# JM_Logics_I2C_SMD_Adapter_v1_4.net
KiCad netlist of a schematic drawn in EAGLE
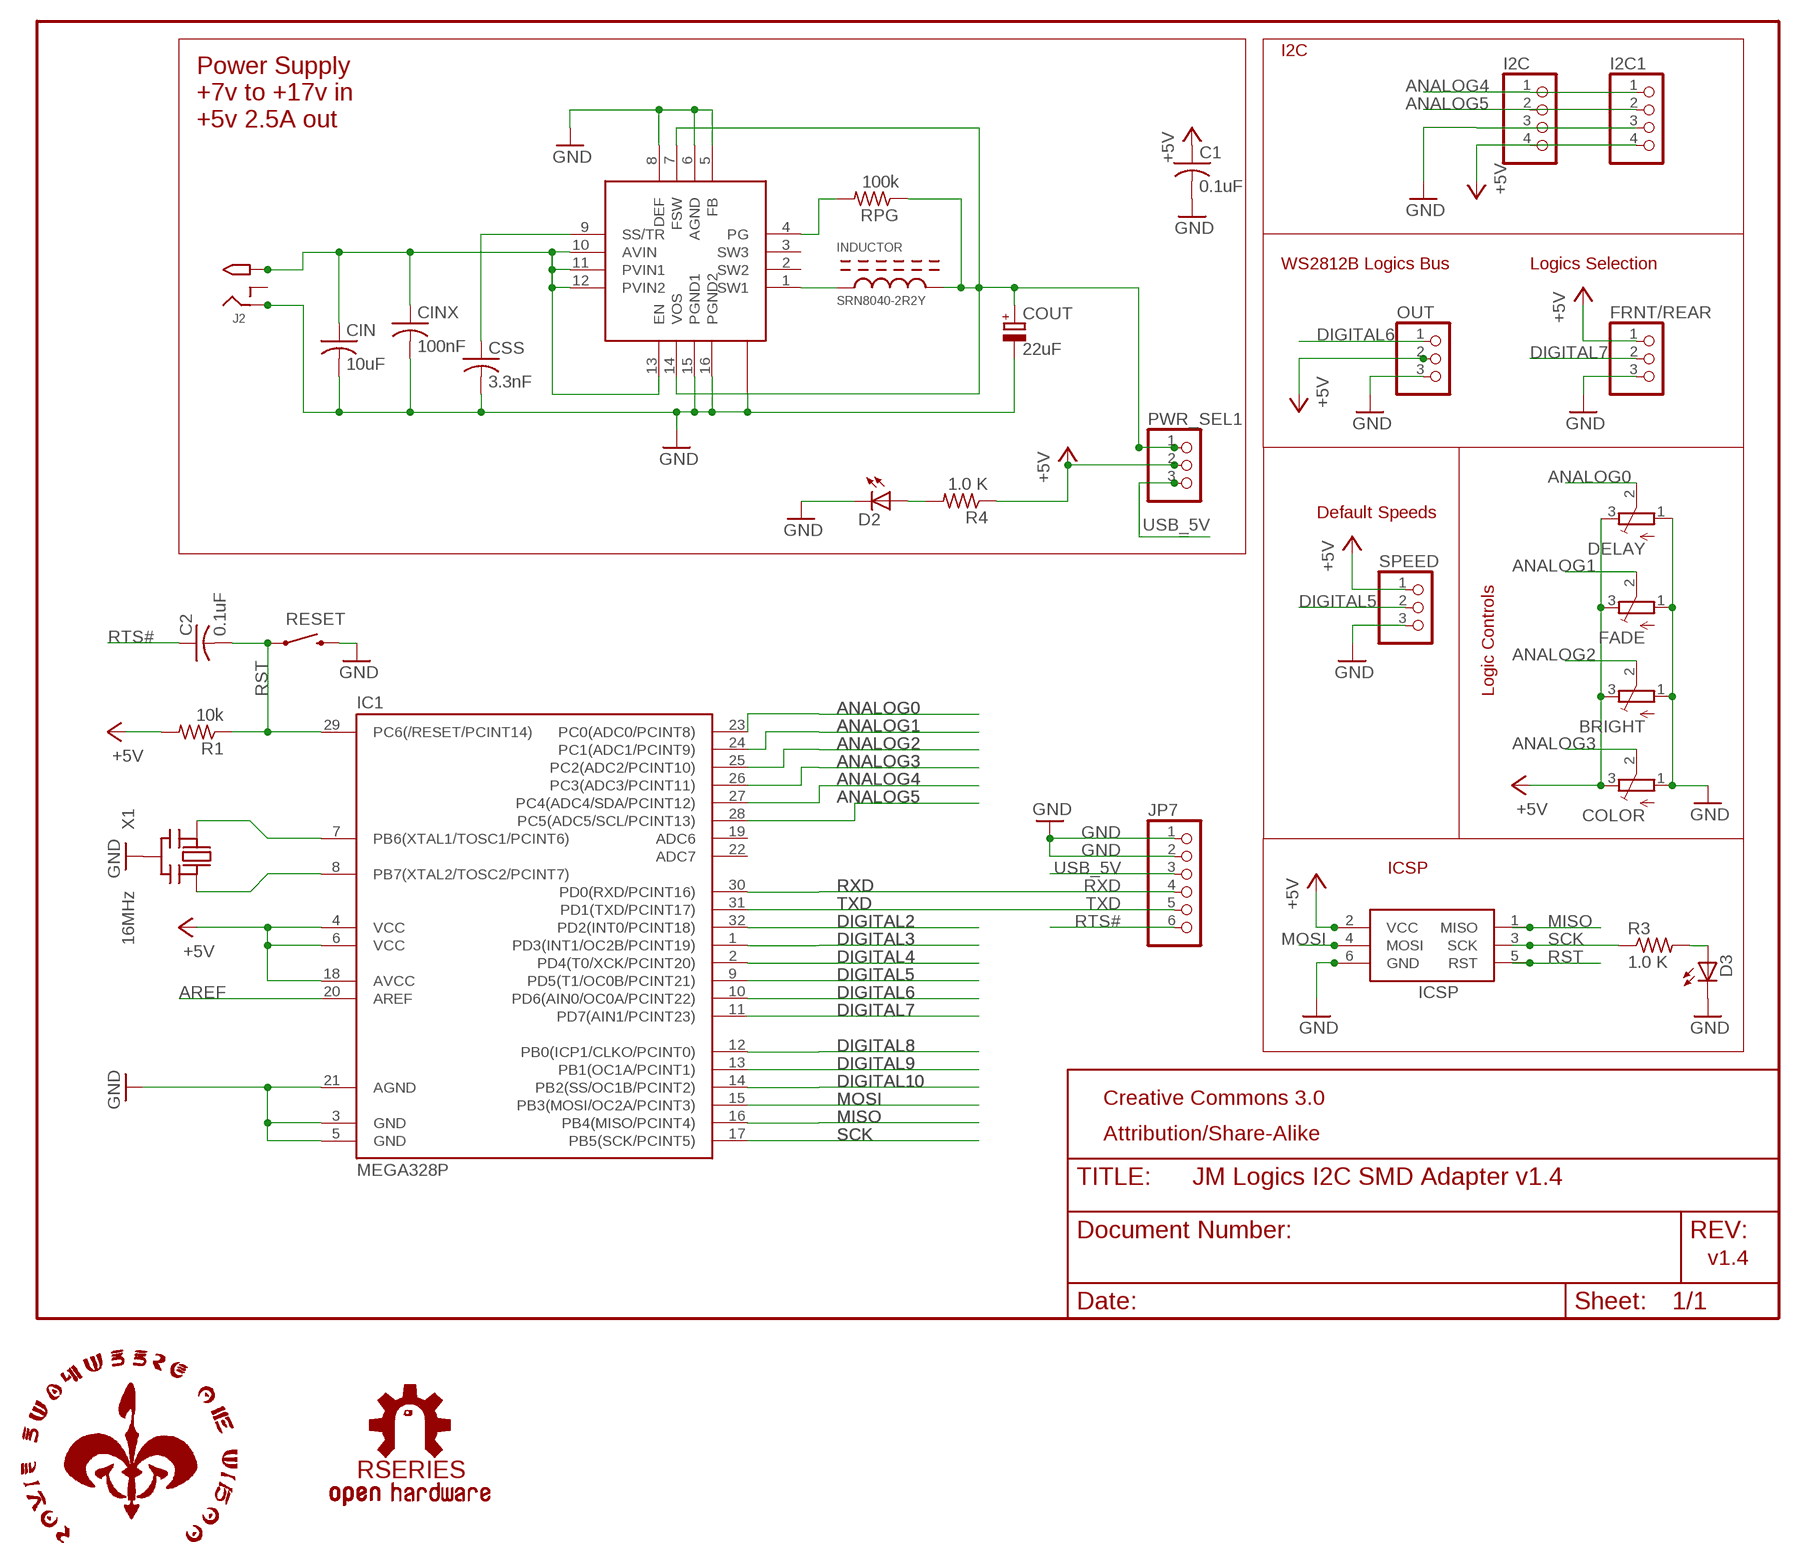
[diagram p0: schematic, sheet 1]

(export (version "E")
  (design (tool "Eeschema 10.0.6"))
  (components
    (comp (ref "BRIGHT")
      (value "TRIMPOTTC33X")
      (footprint "eagle-import:TC33X")
      (libsource (lib "eagle-import") (part "TRIMPOTTC33X"))
    )
    (comp (ref "C1")
      (value "0.1uF")
      (footprint "eagle-import:C1206K")
      (libsource (lib "eagle-import") (part "minimidi_C-USC1206K"))
    )
    (comp (ref "C2")
      (value "0.1uF")
      (footprint "eagle-import:C0805K")
      (libsource (lib "eagle-import") (part "C-USC0805K"))
    )
    (comp (ref "CIN")
      (value "10uF")
      (footprint "eagle-import:C0805K")
      (libsource (lib "eagle-import") (part "C-USC0805K"))
    )
    (comp (ref "CINX")
      (value "100nF")
      (footprint "eagle-import:C0805K")
      (libsource (lib "eagle-import") (part "C-USC0805K"))
    )
    (comp (ref "COLOR")
      (value "TRIMPOTTC33X")
      (footprint "eagle-import:TC33X")
      (libsource (lib "eagle-import") (part "TRIMPOTTC33X"))
    )
    (comp (ref "COUT")
      (value "22uF")
      (footprint "eagle-import:CASE_B")
      (libsource (lib "eagle-import") (part "CAPACITOR_POL-CASE_B"))
    )
    (comp (ref "CSS")
      (value "3.3nF")
      (footprint "eagle-import:C0805K")
      (libsource (lib "eagle-import") (part "C-USC0805K"))
    )
    (comp (ref "D2")
      (value "LEDCHIPLED_1206")
      (footprint "eagle-import:CHIPLED_1206")
      (libsource (lib "eagle-import") (part "LEDCHIPLED_1206"))
    )
    (comp (ref "D3")
      (value "Green")
      (footprint "eagle-import:CHIPLED_1206")
      (libsource (lib "eagle-import") (part "LEDCHIPLED_1206"))
    )
    (comp (ref "DELAY")
      (value "TRIMPOTTC33X")
      (footprint "eagle-import:TC33X")
      (libsource (lib "eagle-import") (part "TRIMPOTTC33X"))
    )
    (comp (ref "FADE")
      (value "TRIMPOTTC33X")
      (footprint "eagle-import:TC33X")
      (libsource (lib "eagle-import") (part "TRIMPOTTC33X"))
    )
    (comp (ref "FRNT/REAR")
      (value "PINHD-1X3")
      (footprint "eagle-import:1X03")
      (libsource (lib "eagle-import") (part "PINHD-1X3"))
    )
    (comp (ref "I2C")
      (value "PINHD-1X4CB")
      (footprint "eagle-import:1X04-CB")
      (libsource (lib "eagle-import") (part "PINHD-1X4CB"))
    )
    (comp (ref "I2C1")
      (value "PINHD-1X4CB")
      (footprint "eagle-import:1X04-CB")
      (libsource (lib "eagle-import") (part "PINHD-1X4CB"))
    )
    (comp (ref "IC1")
      (value "MEGA328P")
      (footprint "eagle-import:TQFP32-08")
      (libsource (lib "eagle-import") (part "MEGA48/88/168-AU"))
    )
    (comp (ref "ICSP")
      (value "AVRISP-6")
      (footprint "eagle-import:AVRISP")
      (libsource (lib "eagle-import") (part "AVRISP-6"))
    )
    (comp (ref "INDUCTOR")
      (value "SRN8040-2R2Y")
      (footprint "eagle-import:SRN8040")
      (libsource (lib "eagle-import") (part "SRN8040"))
    )
    (comp (ref "J2")
      (value "2.1MMJACK")
      (footprint "eagle-import:PJ-102A")
      (libsource (lib "eagle-import") (part "2.1MMJACK"))
    )
    (comp (ref "JP7")
      (value "PINHD-1X6CLEAN")
      (footprint "eagle-import:1X06-CLEAN")
      (libsource (lib "eagle-import") (part "PINHD-1X6CLEAN"))
    )
    (comp (ref "OUT")
      (value "PINHD-1X3")
      (footprint "eagle-import:1X03")
      (libsource (lib "eagle-import") (part "PINHD-1X3"))
    )
    (comp (ref "PWR_SEL1")
      (value "PINHD-1X3")
      (footprint "eagle-import:1X03")
      (libsource (lib "eagle-import") (part "PINHD-1X3"))
    )
    (comp (ref "R1")
      (value "10k")
      (footprint "eagle-import:R0805")
      (libsource (lib "eagle-import") (part "R-US_R0805"))
    )
    (comp (ref "R3")
      (value "1.0 K")
      (footprint "eagle-import:M1206")
      (libsource (lib "eagle-import") (part "minimidi_R-US_M1206"))
    )
    (comp (ref "R4")
      (value "1.0 K")
      (footprint "eagle-import:M1206")
      (libsource (lib "eagle-import") (part "minimidi_R-US_M1206"))
    )
    (comp (ref "REG")
      (value "TPS62133")
      (footprint "eagle-import:TPS6213X")
      (libsource (lib "eagle-import") (part "TPS6213X"))
    )
    (comp (ref "RESET")
      (value "SWITCH-MOMENTARY-2SMD")
      (footprint "eagle-import:TACTILE_SWITCH_SMD")
      (libsource (lib "eagle-import") (part "SWITCH-MOMENTARY-2SMD"))
    )
    (comp (ref "RPG")
      (value "100k")
      (footprint "eagle-import:R0805")
      (libsource (lib "eagle-import") (part "R-US_R0805"))
    )
    (comp (ref "SPEED")
      (value "PINHD-1X3")
      (footprint "eagle-import:1X03")
      (libsource (lib "eagle-import") (part "PINHD-1X3"))
    )
    (comp (ref "U$1")
      (value "ROYAL-ENGINEERS-OF-NABOOSMALL")
      (footprint "eagle-import:ROYAL-ENGINEERS-OF-NABOO-SMALL")
      (libsource (lib "eagle-import") (part "ROYAL-ENGINEERS-OF-NABOOSMALL"))
    )
    (comp (ref "U$2")
      (value "RSERIES-OSHW-LOGOMEDIUM")
      (footprint "eagle-import:RSERIES-OSHW-LOGO-MEDIUM")
      (libsource (lib "eagle-import") (part "RSERIES-OSHW-LOGOMEDIUM"))
    )
    (comp (ref "X1")
      (value "16MHz")
      (footprint "eagle-import:CERM_OSC")
      (libsource (lib "eagle-import") (part "CERMOSCILL"))
    )
  )
  (nets
    (net (code "1") (name "+5V") (class "Default")
      (node (ref "BRIGHT") (pin "3") (pinfunction "E_3") (pintype "passive"))
      (node (ref "C1") (pin "1") (pinfunction "1_1") (pintype "passive"))
      (node (ref "COLOR") (pin "3") (pinfunction "E_3") (pintype "passive"))
      (node (ref "DELAY") (pin "3") (pinfunction "E_3") (pintype "passive"))
      (node (ref "FADE") (pin "3") (pinfunction "E_3") (pintype "passive"))
      (node (ref "FRNT/REAR") (pin "1") (pinfunction "1_1") (pintype "passive"))
      (node (ref "I2C") (pin "4") (pinfunction "4_4") (pintype "passive"))
      (node (ref "I2C1") (pin "4") (pinfunction "4_4") (pintype "passive"))
      (node (ref "IC1") (pin "18") (pinfunction "AVCC_18") (pintype "passive"))
      (node (ref "IC1") (pin "4") (pinfunction "VCC_4") (pintype "power_in"))
      (node (ref "IC1") (pin "6") (pinfunction "VCC_6") (pintype "power_in"))
      (node (ref "ICSP") (pin "2") (pinfunction "VCC_2") (pintype "power_in"))
      (node (ref "OUT") (pin "2") (pinfunction "2_2") (pintype "passive"))
      (node (ref "PWR_SEL1") (pin "2") (pinfunction "2_2") (pintype "passive"))
      (node (ref "R1") (pin "2") (pinfunction "2_2") (pintype "passive"))
      (node (ref "R4") (pin "1") (pinfunction "1_1") (pintype "passive"))
      (node (ref "SPEED") (pin "1") (pinfunction "1_1") (pintype "passive"))
    )
    (net (code "2") (name "/ANALOG0") (class "Default")
      (node (ref "DELAY") (pin "2") (pinfunction "S_2") (pintype "passive"))
      (node (ref "IC1") (pin "23") (pinfunction "PC0(ADC0/PCINT8)_23") (pintype "bidirectional"))
    )
    (net (code "3") (name "/ANALOG1") (class "Default")
      (node (ref "FADE") (pin "2") (pinfunction "S_2") (pintype "passive"))
      (node (ref "IC1") (pin "24") (pinfunction "PC1(ADC1/PCINT9)_24") (pintype "bidirectional"))
    )
    (net (code "4") (name "/ANALOG2") (class "Default")
      (node (ref "BRIGHT") (pin "2") (pinfunction "S_2") (pintype "passive"))
      (node (ref "IC1") (pin "25") (pinfunction "PC2(ADC2/PCINT10)_25") (pintype "bidirectional"))
    )
    (net (code "5") (name "/ANALOG3") (class "Default")
      (node (ref "COLOR") (pin "2") (pinfunction "S_2") (pintype "passive"))
      (node (ref "IC1") (pin "26") (pinfunction "PC3(ADC3/PCINT11)_26") (pintype "bidirectional"))
    )
    (net (code "6") (name "/ANALOG4") (class "Default")
      (node (ref "I2C") (pin "1") (pinfunction "1_1") (pintype "passive"))
      (node (ref "I2C1") (pin "1") (pinfunction "1_1") (pintype "passive"))
      (node (ref "IC1") (pin "27") (pinfunction "PC4(ADC4/SDA/PCINT12)_27") (pintype "bidirectional"))
    )
    (net (code "7") (name "/ANALOG5") (class "Default")
      (node (ref "I2C") (pin "2") (pinfunction "2_2") (pintype "passive"))
      (node (ref "I2C1") (pin "2") (pinfunction "2_2") (pintype "passive"))
      (node (ref "IC1") (pin "28") (pinfunction "PC5(ADC5/SCL/PCINT13)_28") (pintype "bidirectional"))
    )
    (net (code "8") (name "/AREF") (class "Default")
      (node (ref "IC1") (pin "20") (pinfunction "AREF_20") (pintype "passive"))
    )
    (net (code "9") (name "/DIGITAL2") (class "Default")
      (node (ref "IC1") (pin "32") (pinfunction "PD2(INT0/PCINT18)_32") (pintype "bidirectional"))
    )
    (net (code "10") (name "/DIGITAL3") (class "Default")
      (node (ref "IC1") (pin "1") (pinfunction "PD3(INT1/OC2B/PCINT19)_1") (pintype "bidirectional"))
    )
    (net (code "11") (name "/DIGITAL4") (class "Default")
      (node (ref "IC1") (pin "2") (pinfunction "PD4(T0/XCK/PCINT20)_2") (pintype "bidirectional"))
    )
    (net (code "12") (name "/DIGITAL5") (class "Default")
      (node (ref "IC1") (pin "9") (pinfunction "PD5(T1/OC0B/PCINT21)_9") (pintype "bidirectional"))
      (node (ref "SPEED") (pin "2") (pinfunction "2_2") (pintype "passive"))
    )
    (net (code "13") (name "/DIGITAL6") (class "Default")
      (node (ref "IC1") (pin "10") (pinfunction "PD6(AIN0/OC0A/PCINT22)_10") (pintype "bidirectional"))
      (node (ref "OUT") (pin "1") (pinfunction "1_1") (pintype "passive"))
    )
    (net (code "14") (name "/DIGITAL7") (class "Default")
      (node (ref "FRNT/REAR") (pin "2") (pinfunction "2_2") (pintype "passive"))
      (node (ref "IC1") (pin "11") (pinfunction "PD7(AIN1/PCINT23)_11") (pintype "bidirectional"))
    )
    (net (code "15") (name "/DIGITAL8") (class "Default")
      (node (ref "IC1") (pin "12") (pinfunction "PB0(ICP1/CLKO/PCINT0)_12") (pintype "bidirectional"))
    )
    (net (code "16") (name "/DIGITAL9") (class "Default")
      (node (ref "IC1") (pin "13") (pinfunction "PB1(OC1A/PCINT1)_13") (pintype "bidirectional"))
    )
    (net (code "17") (name "/DIGITAL10") (class "Default")
      (node (ref "IC1") (pin "14") (pinfunction "PB2(SS/OC1B/PCINT2)_14") (pintype "bidirectional"))
    )
    (net (code "18") (name "/MISO") (class "Default")
      (node (ref "IC1") (pin "16") (pinfunction "PB4(MISO/PCINT4)_16") (pintype "bidirectional"))
      (node (ref "ICSP") (pin "1") (pinfunction "MISO_1") (pintype "input"))
    )
    (net (code "19") (name "/MOSI") (class "Default")
      (node (ref "IC1") (pin "15") (pinfunction "PB3(MOSI/OC2A/PCINT3)_15") (pintype "bidirectional"))
      (node (ref "ICSP") (pin "4") (pinfunction "MOSI_4") (pintype "output"))
    )
    (net (code "20") (name "/RST") (class "Default")
      (node (ref "C2") (pin "2") (pinfunction "2_2") (pintype "passive"))
      (node (ref "IC1") (pin "29") (pinfunction "PC6(/RESET/PCINT14)_29") (pintype "bidirectional"))
      (node (ref "ICSP") (pin "5") (pinfunction "RST_5") (pintype "output"))
      (node (ref "R1") (pin "1") (pinfunction "1_1") (pintype "passive"))
      (node (ref "RESET") (pin "1") (pinfunction "1_1") (pintype "passive"))
    )
    (net (code "21") (name "/RTS#") (class "Default")
      (node (ref "C2") (pin "1") (pinfunction "1_1") (pintype "passive"))
      (node (ref "JP7") (pin "6") (pinfunction "6_6") (pintype "passive"))
    )
    (net (code "22") (name "/RXD") (class "Default")
      (node (ref "IC1") (pin "30") (pinfunction "PD0(RXD/PCINT16)_30") (pintype "bidirectional"))
      (node (ref "JP7") (pin "4") (pinfunction "4_4") (pintype "passive"))
    )
    (net (code "23") (name "/SCK") (class "Default")
      (node (ref "IC1") (pin "17") (pinfunction "PB5(SCK/PCINT5)_17") (pintype "bidirectional"))
      (node (ref "ICSP") (pin "3") (pinfunction "SCK_3") (pintype "output"))
      (node (ref "R3") (pin "1") (pinfunction "1_1") (pintype "passive"))
    )
    (net (code "24") (name "/TXD") (class "Default")
      (node (ref "IC1") (pin "31") (pinfunction "PD1(TXD/PCINT17)_31") (pintype "bidirectional"))
      (node (ref "JP7") (pin "5") (pinfunction "5_5") (pintype "passive"))
    )
    (net (code "25") (name "/USB_5V") (class "Default")
      (node (ref "JP7") (pin "3") (pinfunction "3_3") (pintype "passive"))
      (node (ref "PWR_SEL1") (pin "3") (pinfunction "3_3") (pintype "passive"))
    )
    (net (code "26") (name "GND") (class "Default")
      (node (ref "BRIGHT") (pin "1") (pinfunction "A_1") (pintype "passive"))
      (node (ref "C1") (pin "2") (pinfunction "2_2") (pintype "passive"))
      (node (ref "CIN") (pin "2") (pinfunction "2_2") (pintype "passive"))
      (node (ref "CINX") (pin "2") (pinfunction "2_2") (pintype "passive"))
      (node (ref "COLOR") (pin "1") (pinfunction "A_1") (pintype "passive"))
      (node (ref "COUT") (pin "-") (pinfunction "-_-") (pintype "passive"))
      (node (ref "CSS") (pin "2") (pinfunction "2_2") (pintype "passive"))
      (node (ref "D2") (pin "C") (pinfunction "C_C") (pintype "passive"))
      (node (ref "D3") (pin "C") (pinfunction "C_C") (pintype "passive"))
      (node (ref "DELAY") (pin "1") (pinfunction "A_1") (pintype "passive"))
      (node (ref "FADE") (pin "1") (pinfunction "A_1") (pintype "passive"))
      (node (ref "FRNT/REAR") (pin "3") (pinfunction "3_3") (pintype "passive"))
      (node (ref "I2C") (pin "3") (pinfunction "3_3") (pintype "passive"))
      (node (ref "I2C1") (pin "3") (pinfunction "3_3") (pintype "passive"))
      (node (ref "IC1") (pin "21") (pinfunction "AGND_21") (pintype "power_in"))
      (node (ref "IC1") (pin "3") (pinfunction "GND_3") (pintype "power_in"))
      (node (ref "IC1") (pin "5") (pinfunction "GND_5") (pintype "power_in"))
      (node (ref "ICSP") (pin "6") (pinfunction "GND_6") (pintype "power_in"))
      (node (ref "J2") (pin "RING") (pinfunction "RING_RING") (pintype "bidirectional"))
      (node (ref "JP7") (pin "1") (pinfunction "1_1") (pintype "passive"))
      (node (ref "JP7") (pin "2") (pinfunction "2_2") (pintype "passive"))
      (node (ref "OUT") (pin "3") (pinfunction "3_3") (pintype "passive"))
      (node (ref "REG") (pin "15") (pinfunction "PGND1_15") (pintype "bidirectional"))
      (node (ref "REG") (pin "16") (pinfunction "PGND2_16") (pintype "bidirectional"))
      (node (ref "REG") (pin "17-THERMALPAD") (pinfunction "THERM_17-THERMALPAD") (pintype "bidirectional"))
      (node (ref "REG") (pin "5") (pinfunction "FB_5") (pintype "bidirectional"))
      (node (ref "REG") (pin "6") (pinfunction "AGND_6") (pintype "bidirectional"))
      (node (ref "REG") (pin "8") (pinfunction "DEF_8") (pintype "bidirectional"))
      (node (ref "RESET") (pin "3") (pinfunction "2_3") (pintype "passive"))
      (node (ref "SPEED") (pin "3") (pinfunction "3_3") (pintype "passive"))
      (node (ref "X1") (pin "P$2") (pinfunction "GND_P$2") (pintype "bidirectional"))
    )
    (net (code "27") (name "Net-(D2-PadA)") (class "Default")
      (node (ref "D2") (pin "A") (pinfunction "A_A") (pintype "passive"))
      (node (ref "R4") (pin "2") (pinfunction "2_2") (pintype "passive"))
    )
    (net (code "28") (name "Net-(D3-PadA)") (class "Default")
      (node (ref "D3") (pin "A") (pinfunction "A_A") (pintype "passive"))
      (node (ref "R3") (pin "2") (pinfunction "2_2") (pintype "passive"))
    )
    (net (code "29") (name "Net-(IC1-PB6(XTAL1{slash}TOSC1{slash}PCINT6))") (class "Default")
      (node (ref "IC1") (pin "7") (pinfunction "PB6(XTAL1/TOSC1/PCINT6)_7") (pintype "bidirectional"))
      (node (ref "X1") (pin "P$1") (pinfunction "IN_P$1") (pintype "bidirectional"))
    )
    (net (code "30") (name "Net-(IC1-PB7(XTAL2{slash}TOSC2{slash}PCINT7))") (class "Default")
      (node (ref "IC1") (pin "8") (pinfunction "PB7(XTAL2/TOSC2/PCINT7)_8") (pintype "bidirectional"))
      (node (ref "X1") (pin "P$3") (pinfunction "OUT_P$3") (pintype "bidirectional"))
    )
    (net (code "31") (name "Net-(INDUCTOR-P1)") (class "Default")
      (node (ref "INDUCTOR") (pin "P$1") (pinfunction "P1_P$1") (pintype "bidirectional"))
      (node (ref "REG") (pin "1") (pinfunction "SW1_1") (pintype "bidirectional"))
    )
    (net (code "32") (name "Net-(INDUCTOR-P2)") (class "Default")
      (node (ref "COUT") (pin "+") (pinfunction "+_+") (pintype "passive"))
      (node (ref "INDUCTOR") (pin "P$2") (pinfunction "P2_P$2") (pintype "bidirectional"))
      (node (ref "PWR_SEL1") (pin "1") (pinfunction "1_1") (pintype "passive"))
      (node (ref "REG") (pin "14") (pinfunction "VOS_14") (pintype "bidirectional"))
      (node (ref "REG") (pin "7") (pinfunction "FSW_7") (pintype "bidirectional"))
      (node (ref "RPG") (pin "1") (pinfunction "1_1") (pintype "passive"))
    )
    (net (code "33") (name "Net-(REG-AVIN)") (class "Default")
      (node (ref "CIN") (pin "1") (pinfunction "1_1") (pintype "passive"))
      (node (ref "CINX") (pin "1") (pinfunction "1_1") (pintype "passive"))
      (node (ref "J2") (pin "TIP") (pinfunction "TIP_TIP") (pintype "bidirectional"))
      (node (ref "REG") (pin "10") (pinfunction "AVIN_10") (pintype "bidirectional"))
      (node (ref "REG") (pin "11") (pinfunction "PVIN1_11") (pintype "bidirectional"))
      (node (ref "REG") (pin "12") (pinfunction "PVIN2_12") (pintype "bidirectional"))
      (node (ref "REG") (pin "13") (pinfunction "EN_13") (pintype "bidirectional"))
    )
    (net (code "34") (name "Net-(REG-PG)") (class "Default")
      (node (ref "REG") (pin "4") (pinfunction "PG_4") (pintype "bidirectional"))
      (node (ref "RPG") (pin "2") (pinfunction "2_2") (pintype "passive"))
    )
    (net (code "35") (name "Net-(REG-SS{slash}TR)") (class "Default")
      (node (ref "CSS") (pin "1") (pinfunction "1_1") (pintype "passive"))
      (node (ref "REG") (pin "9") (pinfunction "SS/TR_9") (pintype "bidirectional"))
    )
    (net (code "36") (name "unconnected-(IC1-ADC6-Pad19)") (class "Default")
      (node (ref "IC1") (pin "19") (pinfunction "ADC6_19") (pintype "passive"))
    )
    (net (code "37") (name "unconnected-(IC1-ADC7-Pad22)") (class "Default")
      (node (ref "IC1") (pin "22") (pinfunction "ADC7_22") (pintype "passive"))
    )
    (net (code "38") (name "unconnected-(J2-PadRING_SW)") (class "Default")
      (node (ref "J2") (pin "RING_SW") (pinfunction "RING_SW_RING_SW") (pintype "bidirectional"))
    )
    (net (code "39") (name "unconnected-(REG-SW2-Pad2)") (class "Default")
      (node (ref "REG") (pin "2") (pinfunction "SW2_2") (pintype "bidirectional"))
    )
    (net (code "40") (name "unconnected-(REG-SW3-Pad3)") (class "Default")
      (node (ref "REG") (pin "3") (pinfunction "SW3_3") (pintype "bidirectional"))
    )
  )
)
